# LPDDR3.net
KiCad netlist of a schematic drawn in Altium Designer
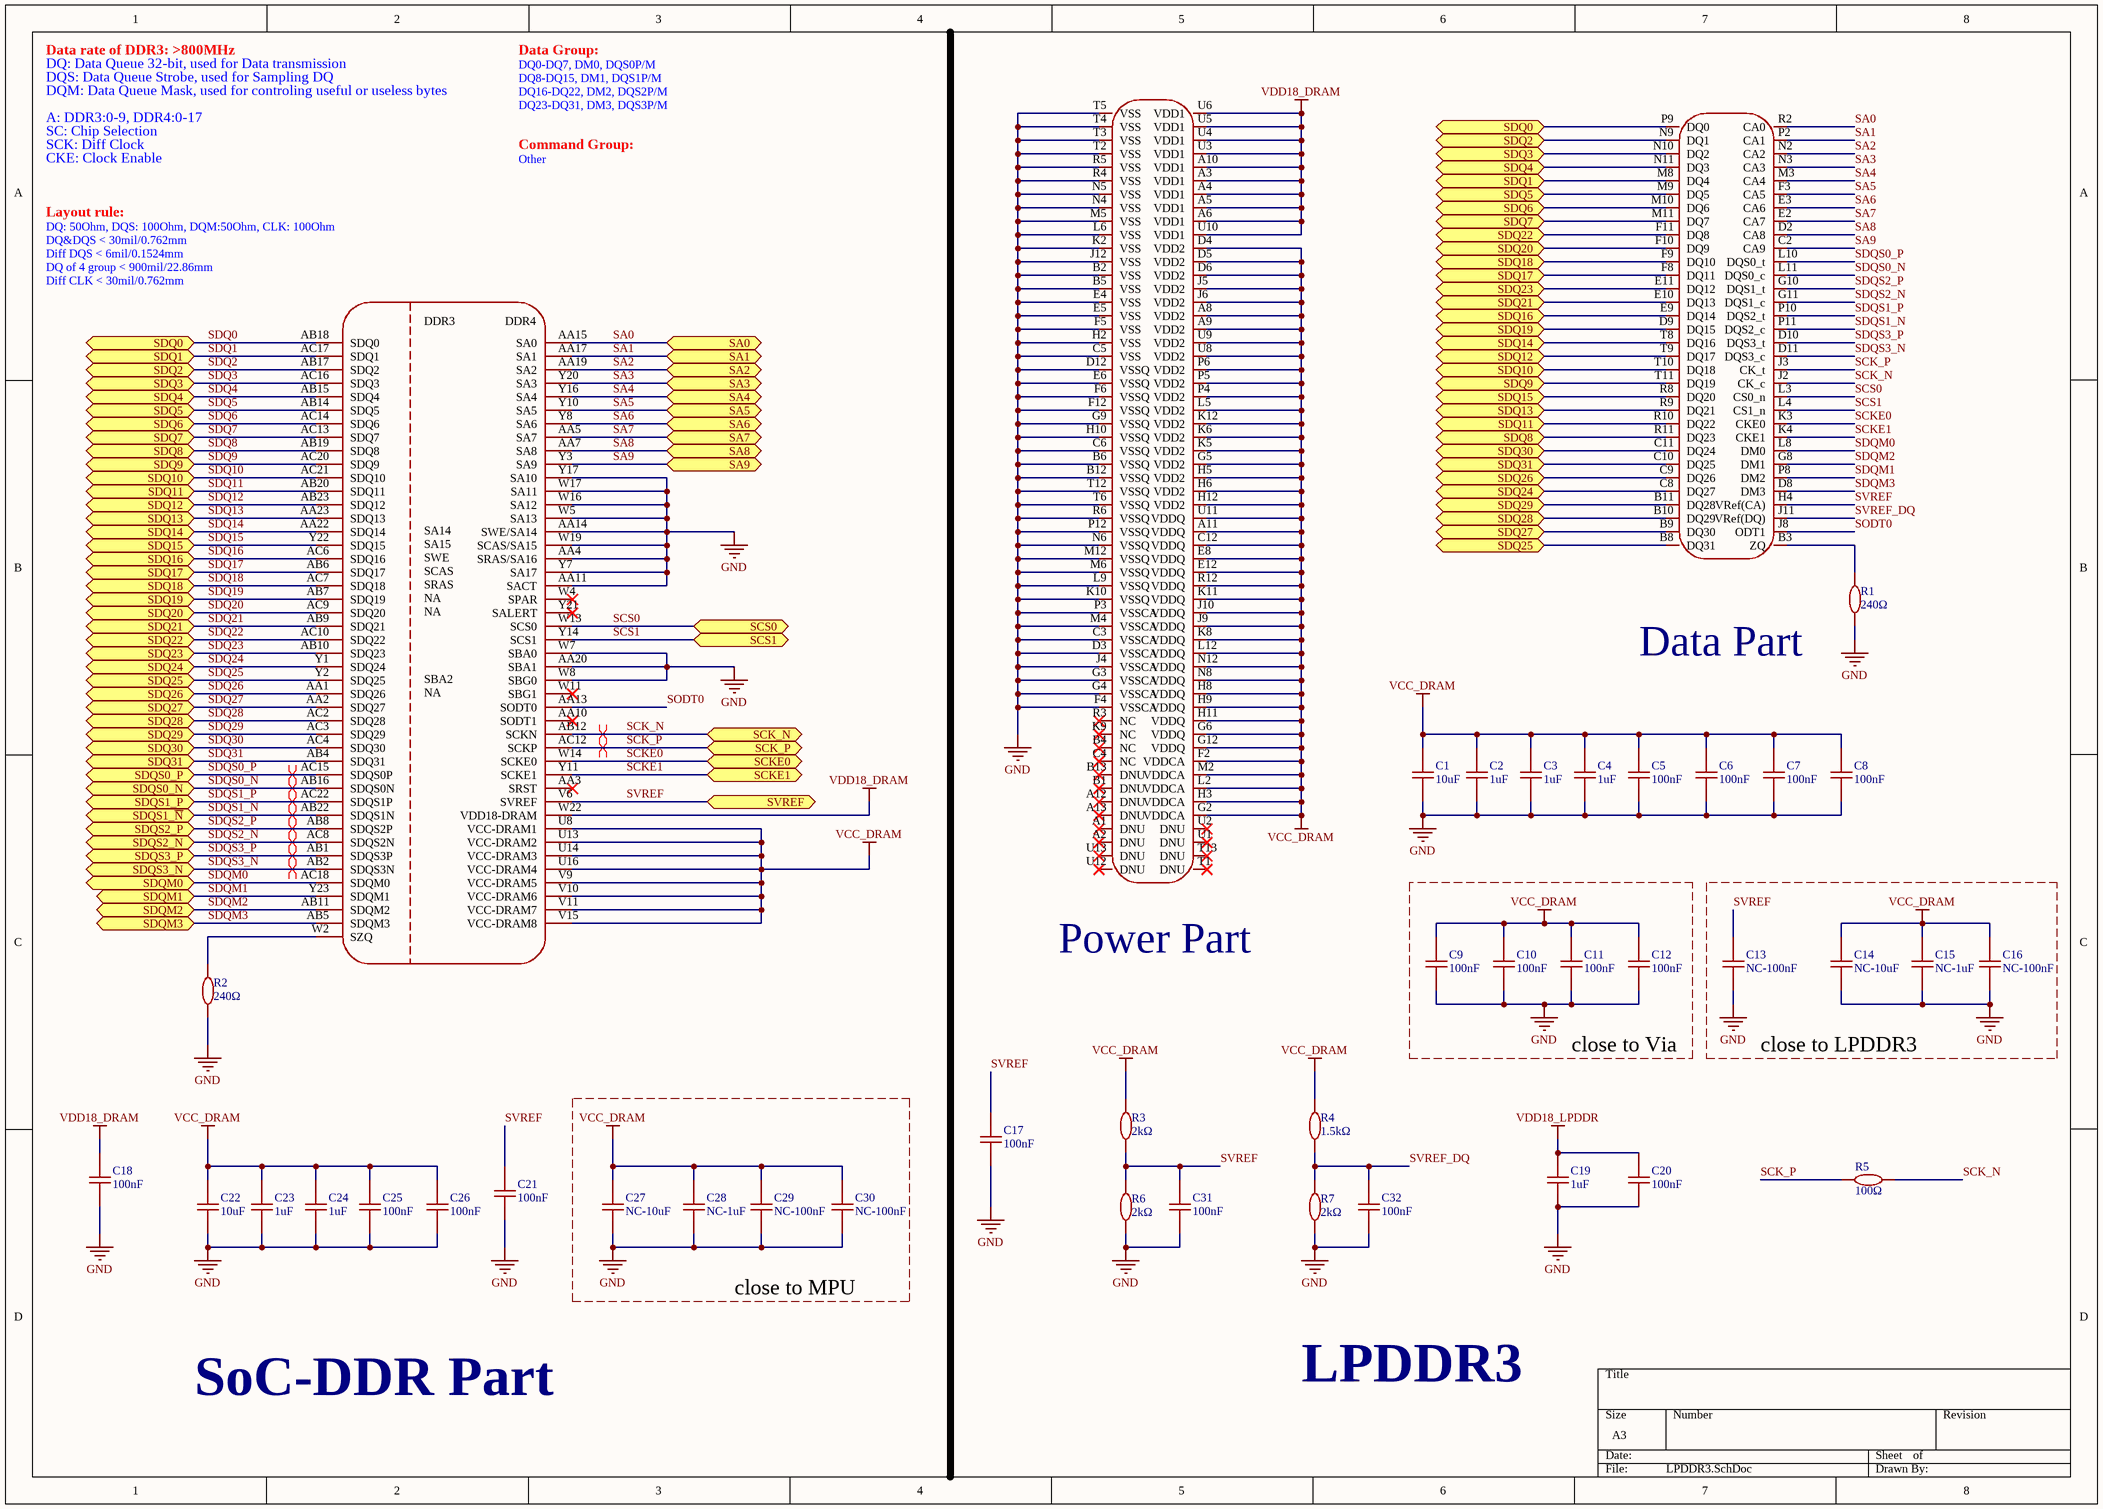
[diagram p0: LPDDR3.SchDoc]

(export (version "E")
  (design (tool "Eeschema 10.0.6"))
  (components
    (comp (ref "C1")
      (value "10uF")
      (footprint "C0603")
      (description "10V 10uF X5R ±10% 0603 Ceramic Capacitors ROHS")
      (libsource (lib "RLC") (part "10uF"))
    )
    (comp (ref "C2")
      (value "1uF")
      (footprint "C0402")
      (description "50V 1uF X5R ±10% 0603 Ceramic Capacitors ROHS")
      (libsource (lib "RLC") (part "1uF"))
    )
    (comp (ref "C3")
      (value "1uF")
      (footprint "C0402")
      (description "50V 1uF X5R ±10% 0603 Ceramic Capacitors ROHS")
      (libsource (lib "RLC") (part "1uF"))
    )
    (comp (ref "C4")
      (value "1uF")
      (footprint "C0402")
      (description "50V 1uF X5R ±10% 0603 Ceramic Capacitors ROHS")
      (libsource (lib "RLC") (part "1uF"))
    )
    (comp (ref "C5")
      (value "100nF")
      (footprint "C0402")
      (description "50V 100nF X7R ±10% 0603 Ceramic Capacitors ROHS")
      (libsource (lib "RLC") (part "100nF"))
    )
    (comp (ref "C6")
      (value "100nF")
      (footprint "C0402")
      (description "50V 100nF X7R ±10% 0603 Ceramic Capacitors ROHS")
      (libsource (lib "RLC") (part "100nF"))
    )
    (comp (ref "C7")
      (value "100nF")
      (footprint "C0402")
      (description "50V 100nF X7R ±10% 0603 Ceramic Capacitors ROHS")
      (libsource (lib "RLC") (part "100nF"))
    )
    (comp (ref "C8")
      (value "100nF")
      (footprint "C0402")
      (description "50V 100nF X7R ±10% 0603 Ceramic Capacitors ROHS")
      (libsource (lib "RLC") (part "100nF"))
    )
    (comp (ref "C9")
      (value "100nF")
      (footprint "C0402")
      (description "50V 100nF X7R ±10% 0603 Ceramic Capacitors ROHS")
      (libsource (lib "RLC") (part "100nF"))
    )
    (comp (ref "C10")
      (value "100nF")
      (footprint "C0402")
      (description "50V 100nF X7R ±10% 0603 Ceramic Capacitors ROHS")
      (libsource (lib "RLC") (part "100nF"))
    )
    (comp (ref "C11")
      (value "100nF")
      (footprint "C0402")
      (description "50V 100nF X7R ±10% 0603 Ceramic Capacitors ROHS")
      (libsource (lib "RLC") (part "100nF"))
    )
    (comp (ref "C12")
      (value "100nF")
      (footprint "C0402")
      (description "50V 100nF X7R ±10% 0603 Ceramic Capacitors ROHS")
      (libsource (lib "RLC") (part "100nF"))
    )
    (comp (ref "C13")
      (value "NC-100nF")
      (footprint "C0402")
      (description "50V 100nF X7R ±10% 0603 Ceramic Capacitors ROHS")
      (libsource (lib "RLC") (part "100nF"))
    )
    (comp (ref "C14")
      (value "NC-10uF")
      (footprint "C0603")
      (description "10V 10uF X5R ±10% 0603 Ceramic Capacitors ROHS")
      (libsource (lib "RLC") (part "10uF"))
    )
    (comp (ref "C15")
      (value "NC-1uF")
      (footprint "C0402")
      (description "50V 1uF X5R ±10% 0603 Ceramic Capacitors ROHS")
      (libsource (lib "RLC") (part "1uF"))
    )
    (comp (ref "C16")
      (value "NC-100nF")
      (footprint "C0402")
      (description "50V 100nF X7R ±10% 0603 Ceramic Capacitors ROHS")
      (libsource (lib "RLC") (part "100nF"))
    )
    (comp (ref "C17")
      (value "100nF")
      (footprint "C0402")
      (description "50V 100nF X7R ±10% 0603 Ceramic Capacitors ROHS")
      (libsource (lib "RLC") (part "100nF"))
    )
    (comp (ref "C18")
      (value "100nF")
      (footprint "C0402")
      (description "50V 100nF X7R ±10% 0603 Ceramic Capacitors ROHS")
      (libsource (lib "RLC") (part "100nF"))
    )
    (comp (ref "C19")
      (value "1uF")
      (footprint "C0402")
      (description "50V 1uF X5R ±10% 0603 Ceramic Capacitors ROHS")
      (libsource (lib "RLC") (part "1uF"))
    )
    (comp (ref "C20")
      (value "100nF")
      (footprint "C0402")
      (description "50V 100nF X7R ±10% 0603 Ceramic Capacitors ROHS")
      (libsource (lib "RLC") (part "100nF"))
    )
    (comp (ref "C21")
      (value "100nF")
      (footprint "C0402")
      (description "50V 100nF X7R ±10% 0603 Ceramic Capacitors ROHS")
      (libsource (lib "RLC") (part "100nF"))
    )
    (comp (ref "C22")
      (value "10uF")
      (footprint "C0603")
      (description "10V 10uF X5R ±10% 0603 Ceramic Capacitors ROHS")
      (libsource (lib "RLC") (part "10uF"))
    )
    (comp (ref "C23")
      (value "1uF")
      (footprint "C0402")
      (description "50V 1uF X5R ±10% 0603 Ceramic Capacitors ROHS")
      (libsource (lib "RLC") (part "1uF"))
    )
    (comp (ref "C24")
      (value "1uF")
      (footprint "C0402")
      (description "50V 1uF X5R ±10% 0603 Ceramic Capacitors ROHS")
      (libsource (lib "RLC") (part "1uF"))
    )
    (comp (ref "C25")
      (value "100nF")
      (footprint "C0402")
      (description "50V 100nF X7R ±10% 0603 Ceramic Capacitors ROHS")
      (libsource (lib "RLC") (part "100nF"))
    )
    (comp (ref "C26")
      (value "100nF")
      (footprint "C0402")
      (description "50V 100nF X7R ±10% 0603 Ceramic Capacitors ROHS")
      (libsource (lib "RLC") (part "100nF"))
    )
    (comp (ref "C27")
      (value "NC-10uF")
      (footprint "C0603")
      (description "10V 10uF X5R ±10% 0603 Ceramic Capacitors ROHS")
      (libsource (lib "RLC") (part "10uF"))
    )
    (comp (ref "C28")
      (value "NC-1uF")
      (footprint "C0402")
      (description "50V 1uF X5R ±10% 0603 Ceramic Capacitors ROHS")
      (libsource (lib "RLC") (part "1uF"))
    )
    (comp (ref "C29")
      (value "NC-100nF")
      (footprint "C0402")
      (description "50V 100nF X7R ±10% 0603 Ceramic Capacitors ROHS")
      (libsource (lib "RLC") (part "100nF"))
    )
    (comp (ref "C30")
      (value "NC-100nF")
      (footprint "C0402")
      (description "50V 100nF X7R ±10% 0603 Ceramic Capacitors ROHS")
      (libsource (lib "RLC") (part "100nF"))
    )
    (comp (ref "C31")
      (value "100nF")
      (footprint "C0402")
      (description "50V 100nF X7R ±10% 0402 Ceramic Capacitors ROHS")
      (libsource (lib "RLC") (part "100nF"))
    )
    (comp (ref "C32")
      (value "100nF")
      (footprint "C0402")
      (description "50V 100nF X7R ±10% 0402 Ceramic Capacitors ROHS")
      (libsource (lib "RLC") (part "100nF"))
    )
    (comp (ref "R1")
      (value "240Ω")
      (footprint "R0402")
      (description "240Ω 62.5mW 50V ±100ppm/℃ Thick Film Resistor ±1% 0402 Chip Resistor - Surface Mount ROHS")
      (libsource (lib "RLC") (part "240Ω"))
    )
    (comp (ref "R2")
      (value "240Ω")
      (footprint "R0402")
      (description "240Ω 62.5mW 50V ±100ppm/℃ Thick Film Resistor ±1% 0402 Chip Resistor - Surface Mount ROHS")
      (libsource (lib "RLC") (part "240Ω"))
    )
    (comp (ref "R3")
      (value "2kΩ")
      (footprint "R0402")
      (description "100mW 2kΩ 75V ±100ppm/℃ Thick Film Resistor ±1% 0402 Chip Resistor - Surface Mount ROHS")
      (libsource (lib "RLC") (part "2kΩ"))
    )
    (comp (ref "R4")
      (value "1.5kΩ")
      (footprint "R0402")
      (description "62.5mW 1.5kΩ 50V ±100ppm/℃ Thick Film Resistor ±1% 0402 Chip Resistor - Surface Mount ROHS")
      (libsource (lib "RLC") (part "1.5kΩ"))
    )
    (comp (ref "R5")
      (value "100Ω")
      (footprint "R0402")
      (description "100Ω 62.5mW 50V ±100ppm/℃ Thick Film Resistor ±1% 0402 Chip Resistor - Surface Mount ROHS")
      (libsource (lib "RLC") (part "100Ω"))
    )
    (comp (ref "R6")
      (value "2kΩ")
      (footprint "R0402")
      (description "100mW 2kΩ 75V ±100ppm/℃ Thick Film Resistor ±1% 0402 Chip Resistor - Surface Mount ROHS")
      (libsource (lib "RLC") (part "2kΩ"))
    )
    (comp (ref "R7")
      (value "2kΩ")
      (footprint "R0402")
      (description "100mW 2kΩ 75V ±100ppm/℃ Thick Film Resistor ±1% 0402 Chip Resistor - Surface Mount ROHS")
      (libsource (lib "RLC") (part "2kΩ"))
    )
    (comp (ref "U1")
      (value "LPDDR3-2G")
      (footprint "FBGA-178_L11.5-W11.0_K4E6E304EC-TL")
      (fields
        (field (name "MANUFACTURER") "SAMSUNG(三星半导体)")
        (field (name "MANUFACTURER PART") "K4E6E304EC-EGCG")
      )
      (libsource (lib "IC") (part "LPDDR3-2G"))
    )
    (comp (ref "U2")
      (value "Allwinner_H6")
      (footprint "BGA451_ALLWINNER_H6")
      (libsource (lib "IC") (part "Allwinner_H6"))
    )
  )
  (nets
    (net (code "1") (name "/SA0") (class "Default")
      (node (ref "U1") (pin "R2") (pinfunction "CA0_R2") (pintype "passive"))
      (node (ref "U2") (pin "AA15") (pinfunction "SA0_AA15") (pintype "passive"))
    )
    (net (code "2") (name "/SA1") (class "Default")
      (node (ref "U1") (pin "P2") (pinfunction "CA1_P2") (pintype "passive"))
      (node (ref "U2") (pin "AA17") (pinfunction "SA1_AA17") (pintype "passive"))
    )
    (net (code "3") (name "/SA2") (class "Default")
      (node (ref "U1") (pin "N2") (pinfunction "CA2_N2") (pintype "passive"))
      (node (ref "U2") (pin "AA19") (pinfunction "SA2_AA19") (pintype "passive"))
    )
    (net (code "4") (name "/SA3") (class "Default")
      (node (ref "U1") (pin "N3") (pinfunction "CA3_N3") (pintype "passive"))
      (node (ref "U2") (pin "Y20") (pinfunction "SA3_Y20") (pintype "passive"))
    )
    (net (code "5") (name "/SA4") (class "Default")
      (node (ref "U1") (pin "M3") (pinfunction "CA4_M3") (pintype "passive"))
      (node (ref "U2") (pin "Y16") (pinfunction "SA4_Y16") (pintype "passive"))
    )
    (net (code "6") (name "/SA5") (class "Default")
      (node (ref "U1") (pin "F3") (pinfunction "CA5_F3") (pintype "passive"))
      (node (ref "U2") (pin "Y10") (pinfunction "SA5_Y10") (pintype "passive"))
    )
    (net (code "7") (name "/SA6") (class "Default")
      (node (ref "U1") (pin "E3") (pinfunction "CA6_E3") (pintype "passive"))
      (node (ref "U2") (pin "Y8") (pinfunction "SA6_Y8") (pintype "passive"))
    )
    (net (code "8") (name "/SA7") (class "Default")
      (node (ref "U1") (pin "E2") (pinfunction "CA7_E2") (pintype "passive"))
      (node (ref "U2") (pin "AA5") (pinfunction "SA7_AA5") (pintype "passive"))
    )
    (net (code "9") (name "/SA8") (class "Default")
      (node (ref "U1") (pin "D2") (pinfunction "CA8_D2") (pintype "passive"))
      (node (ref "U2") (pin "AA7") (pinfunction "SA8_AA7") (pintype "passive"))
    )
    (net (code "10") (name "/SA9") (class "Default")
      (node (ref "U1") (pin "C2") (pinfunction "CA9_C2") (pintype "passive"))
      (node (ref "U2") (pin "Y3") (pinfunction "SA9_Y3") (pintype "passive"))
    )
    (net (code "11") (name "/SCKE0") (class "Default")
      (node (ref "U1") (pin "K3") (pinfunction "CKE0_K3") (pintype "passive"))
      (node (ref "U2") (pin "W14") (pinfunction "SCKE0_W14") (pintype "passive"))
    )
    (net (code "12") (name "/SCKE1") (class "Default")
      (node (ref "U1") (pin "K4") (pinfunction "CKE1_K4") (pintype "passive"))
      (node (ref "U2") (pin "Y11") (pinfunction "SCKE1_Y11") (pintype "passive"))
    )
    (net (code "13") (name "/SCK_N") (class "Default")
      (node (ref "R5") (pin "2") (pinfunction "2_2") (pintype "passive"))
      (node (ref "U1") (pin "J2") (pinfunction "CK_c_J2") (pintype "passive"))
      (node (ref "U2") (pin "AB12") (pinfunction "SCKN_AB12") (pintype "passive"))
    )
    (net (code "14") (name "/SCK_P") (class "Default")
      (node (ref "R5") (pin "1") (pinfunction "1_1") (pintype "passive"))
      (node (ref "U1") (pin "J3") (pinfunction "CK_t_J3") (pintype "passive"))
      (node (ref "U2") (pin "AC12") (pinfunction "SCKP_AC12") (pintype "passive"))
    )
    (net (code "15") (name "/SCS0") (class "Default")
      (node (ref "U1") (pin "L3") (pinfunction "CS0_n_L3") (pintype "passive"))
      (node (ref "U2") (pin "W13") (pinfunction "SCS0_W13") (pintype "passive"))
    )
    (net (code "16") (name "/SCS1") (class "Default")
      (node (ref "U1") (pin "L4") (pinfunction "CS1_n_L4") (pintype "passive"))
      (node (ref "U2") (pin "Y14") (pinfunction "SCS1_Y14") (pintype "passive"))
    )
    (net (code "17") (name "/SDQ0") (class "Default")
      (node (ref "U1") (pin "P9") (pinfunction "DQ0_P9") (pintype "passive"))
      (node (ref "U2") (pin "AB18") (pinfunction "SDQ0_AB18") (pintype "passive"))
    )
    (net (code "18") (name "/SDQ1") (class "Default")
      (node (ref "U1") (pin "M8") (pinfunction "DQ4_M8") (pintype "passive"))
      (node (ref "U2") (pin "AC17") (pinfunction "SDQ1_AC17") (pintype "passive"))
    )
    (net (code "19") (name "/SDQ2") (class "Default")
      (node (ref "U1") (pin "N9") (pinfunction "DQ1_N9") (pintype "passive"))
      (node (ref "U2") (pin "AB17") (pinfunction "SDQ2_AB17") (pintype "passive"))
    )
    (net (code "20") (name "/SDQ3") (class "Default")
      (node (ref "U1") (pin "N10") (pinfunction "DQ2_N10") (pintype "passive"))
      (node (ref "U2") (pin "AC16") (pinfunction "SDQ3_AC16") (pintype "passive"))
    )
    (net (code "21") (name "/SDQ4") (class "Default")
      (node (ref "U1") (pin "N11") (pinfunction "DQ3_N11") (pintype "passive"))
      (node (ref "U2") (pin "AB15") (pinfunction "SDQ4_AB15") (pintype "passive"))
    )
    (net (code "22") (name "/SDQ5") (class "Default")
      (node (ref "U1") (pin "M9") (pinfunction "DQ5_M9") (pintype "passive"))
      (node (ref "U2") (pin "AB14") (pinfunction "SDQ5_AB14") (pintype "passive"))
    )
    (net (code "23") (name "/SDQ6") (class "Default")
      (node (ref "U1") (pin "M10") (pinfunction "DQ6_M10") (pintype "passive"))
      (node (ref "U2") (pin "AC14") (pinfunction "SDQ6_AC14") (pintype "passive"))
    )
    (net (code "24") (name "/SDQ7") (class "Default")
      (node (ref "U1") (pin "M11") (pinfunction "DQ7_M11") (pintype "passive"))
      (node (ref "U2") (pin "AC13") (pinfunction "SDQ7_AC13") (pintype "passive"))
    )
    (net (code "25") (name "/SDQ8") (class "Default")
      (node (ref "U1") (pin "R11") (pinfunction "DQ23_R11") (pintype "passive"))
      (node (ref "U2") (pin "AB19") (pinfunction "SDQ8_AB19") (pintype "passive"))
    )
    (net (code "26") (name "/SDQ9") (class "Default")
      (node (ref "U1") (pin "T11") (pinfunction "DQ19_T11") (pintype "passive"))
      (node (ref "U2") (pin "AC20") (pinfunction "SDQ9_AC20") (pintype "passive"))
    )
    (net (code "27") (name "/SDQ10") (class "Default")
      (node (ref "U1") (pin "T10") (pinfunction "DQ18_T10") (pintype "passive"))
      (node (ref "U2") (pin "AC21") (pinfunction "SDQ10_AC21") (pintype "passive"))
    )
    (net (code "28") (name "/SDQ11") (class "Default")
      (node (ref "U1") (pin "R10") (pinfunction "DQ22_R10") (pintype "passive"))
      (node (ref "U2") (pin "AB20") (pinfunction "SDQ11_AB20") (pintype "passive"))
    )
    (net (code "29") (name "/SDQ12") (class "Default")
      (node (ref "U1") (pin "T9") (pinfunction "DQ17_T9") (pintype "passive"))
      (node (ref "U2") (pin "AB23") (pinfunction "SDQ12_AB23") (pintype "passive"))
    )
    (net (code "30") (name "/SDQ13") (class "Default")
      (node (ref "U1") (pin "R9") (pinfunction "DQ21_R9") (pintype "passive"))
      (node (ref "U2") (pin "AA23") (pinfunction "SDQ13_AA23") (pintype "passive"))
    )
    (net (code "31") (name "/SDQ14") (class "Default")
      (node (ref "U1") (pin "T8") (pinfunction "DQ16_T8") (pintype "passive"))
      (node (ref "U2") (pin "AA22") (pinfunction "SDQ14_AA22") (pintype "passive"))
    )
    (net (code "32") (name "/SDQ15") (class "Default")
      (node (ref "U1") (pin "R8") (pinfunction "DQ20_R8") (pintype "passive"))
      (node (ref "U2") (pin "Y22") (pinfunction "SDQ15_Y22") (pintype "passive"))
    )
    (net (code "33") (name "/SDQ16") (class "Default")
      (node (ref "U1") (pin "E9") (pinfunction "DQ14_E9") (pintype "passive"))
      (node (ref "U2") (pin "AC6") (pinfunction "SDQ16_AC6") (pintype "passive"))
    )
    (net (code "34") (name "/SDQ17") (class "Default")
      (node (ref "U1") (pin "F8") (pinfunction "DQ11_F8") (pintype "passive"))
      (node (ref "U2") (pin "AB6") (pinfunction "SDQ17_AB6") (pintype "passive"))
    )
    (net (code "35") (name "/SDQ18") (class "Default")
      (node (ref "U1") (pin "F9") (pinfunction "DQ10_F9") (pintype "passive"))
      (node (ref "U2") (pin "AC7") (pinfunction "SDQ18_AC7") (pintype "passive"))
    )
    (net (code "36") (name "/SDQ19") (class "Default")
      (node (ref "U1") (pin "D9") (pinfunction "DQ15_D9") (pintype "passive"))
      (node (ref "U2") (pin "AB7") (pinfunction "SDQ19_AB7") (pintype "passive"))
    )
    (net (code "37") (name "/SDQ20") (class "Default")
      (node (ref "U1") (pin "F10") (pinfunction "DQ9_F10") (pintype "passive"))
      (node (ref "U2") (pin "AC9") (pinfunction "SDQ20_AC9") (pintype "passive"))
    )
    (net (code "38") (name "/SDQ21") (class "Default")
      (node (ref "U1") (pin "E10") (pinfunction "DQ13_E10") (pintype "passive"))
      (node (ref "U2") (pin "AB9") (pinfunction "SDQ21_AB9") (pintype "passive"))
    )
    (net (code "39") (name "/SDQ22") (class "Default")
      (node (ref "U1") (pin "F11") (pinfunction "DQ8_F11") (pintype "passive"))
      (node (ref "U2") (pin "AC10") (pinfunction "SDQ22_AC10") (pintype "passive"))
    )
    (net (code "40") (name "/SDQ23") (class "Default")
      (node (ref "U1") (pin "E11") (pinfunction "DQ12_E11") (pintype "passive"))
      (node (ref "U2") (pin "AB10") (pinfunction "SDQ23_AB10") (pintype "passive"))
    )
    (net (code "41") (name "/SDQ24") (class "Default")
      (node (ref "U1") (pin "C8") (pinfunction "DQ27_C8") (pintype "passive"))
      (node (ref "U2") (pin "Y1") (pinfunction "SDQ24_Y1") (pintype "passive"))
    )
    (net (code "42") (name "/SDQ25") (class "Default")
      (node (ref "U1") (pin "B8") (pinfunction "DQ31_B8") (pintype "passive"))
      (node (ref "U2") (pin "Y2") (pinfunction "SDQ25_Y2") (pintype "passive"))
    )
    (net (code "43") (name "/SDQ26") (class "Default")
      (node (ref "U1") (pin "C9") (pinfunction "DQ26_C9") (pintype "passive"))
      (node (ref "U2") (pin "AA1") (pinfunction "SDQ26_AA1") (pintype "passive"))
    )
    (net (code "44") (name "/SDQ27") (class "Default")
      (node (ref "U1") (pin "B9") (pinfunction "DQ30_B9") (pintype "passive"))
      (node (ref "U2") (pin "AA2") (pinfunction "SDQ27_AA2") (pintype "passive"))
    )
    (net (code "45") (name "/SDQ28") (class "Default")
      (node (ref "U1") (pin "B10") (pinfunction "DQ29_B10") (pintype "passive"))
      (node (ref "U2") (pin "AC2") (pinfunction "SDQ28_AC2") (pintype "passive"))
    )
    (net (code "46") (name "/SDQ29") (class "Default")
      (node (ref "U1") (pin "B11") (pinfunction "DQ28_B11") (pintype "passive"))
      (node (ref "U2") (pin "AC3") (pinfunction "SDQ29_AC3") (pintype "passive"))
    )
    (net (code "47") (name "/SDQ30") (class "Default")
      (node (ref "U1") (pin "C11") (pinfunction "DQ24_C11") (pintype "passive"))
      (node (ref "U2") (pin "AC4") (pinfunction "SDQ30_AC4") (pintype "passive"))
    )
    (net (code "48") (name "/SDQ31") (class "Default")
      (node (ref "U1") (pin "C10") (pinfunction "DQ25_C10") (pintype "passive"))
      (node (ref "U2") (pin "AB4") (pinfunction "SDQ31_AB4") (pintype "passive"))
    )
    (net (code "49") (name "/SDQM0") (class "Default")
      (node (ref "U1") (pin "L8") (pinfunction "DM0_L8") (pintype "passive"))
      (node (ref "U2") (pin "AC18") (pinfunction "SDQM0_AC18") (pintype "passive"))
    )
    (net (code "50") (name "/SDQM1") (class "Default")
      (node (ref "U1") (pin "P8") (pinfunction "DM2_P8") (pintype "passive"))
      (node (ref "U2") (pin "Y23") (pinfunction "SDQM1_Y23") (pintype "passive"))
    )
    (net (code "51") (name "/SDQM2") (class "Default")
      (node (ref "U1") (pin "G8") (pinfunction "DM1_G8") (pintype "passive"))
      (node (ref "U2") (pin "AB11") (pinfunction "SDQM2_AB11") (pintype "passive"))
    )
    (net (code "52") (name "/SDQM3") (class "Default")
      (node (ref "U1") (pin "D8") (pinfunction "DM3_D8") (pintype "passive"))
      (node (ref "U2") (pin "AB5") (pinfunction "SDQM3_AB5") (pintype "passive"))
    )
    (net (code "53") (name "/SDQS0_N") (class "Default")
      (node (ref "U1") (pin "L11") (pinfunction "DQS0_c_L11") (pintype "passive"))
      (node (ref "U2") (pin "AB16") (pinfunction "SDQS0N_AB16") (pintype "passive"))
    )
    (net (code "54") (name "/SDQS0_P") (class "Default")
      (node (ref "U1") (pin "L10") (pinfunction "DQS0_t_L10") (pintype "passive"))
      (node (ref "U2") (pin "AC15") (pinfunction "SDQS0P_AC15") (pintype "passive"))
    )
    (net (code "55") (name "/SDQS1_N") (class "Default")
      (node (ref "U1") (pin "P11") (pinfunction "DQS2_c_P11") (pintype "passive"))
      (node (ref "U2") (pin "AB22") (pinfunction "SDQS1N_AB22") (pintype "passive"))
    )
    (net (code "56") (name "/SDQS1_P") (class "Default")
      (node (ref "U1") (pin "P10") (pinfunction "DQS2_t_P10") (pintype "passive"))
      (node (ref "U2") (pin "AC22") (pinfunction "SDQS1P_AC22") (pintype "passive"))
    )
    (net (code "57") (name "/SDQS2_N") (class "Default")
      (node (ref "U1") (pin "G11") (pinfunction "DQS1_c_G11") (pintype "passive"))
      (node (ref "U2") (pin "AC8") (pinfunction "SDQS2N_AC8") (pintype "passive"))
    )
    (net (code "58") (name "/SDQS2_P") (class "Default")
      (node (ref "U1") (pin "G10") (pinfunction "DQS1_t_G10") (pintype "passive"))
      (node (ref "U2") (pin "AB8") (pinfunction "SDQS2P_AB8") (pintype "passive"))
    )
    (net (code "59") (name "/SDQS3_N") (class "Default")
      (node (ref "U1") (pin "D11") (pinfunction "DQS3_c_D11") (pintype "passive"))
      (node (ref "U2") (pin "AB2") (pinfunction "SDQS3N_AB2") (pintype "passive"))
    )
    (net (code "60") (name "/SDQS3_P") (class "Default")
      (node (ref "U1") (pin "D10") (pinfunction "DQS3_t_D10") (pintype "passive"))
      (node (ref "U2") (pin "AB1") (pinfunction "SDQS3P_AB1") (pintype "passive"))
    )
    (net (code "61") (name "/SODT0") (class "Default")
      (node (ref "U1") (pin "J8") (pinfunction "ODT1_J8") (pintype "passive"))
      (node (ref "U2") (pin "AA13") (pinfunction "SODT0_AA13") (pintype "passive"))
    )
    (net (code "62") (name "/SVREF") (class "Default")
      (node (ref "C13") (pin "2") (pinfunction "2_2") (pintype "passive"))
      (node (ref "C17") (pin "2") (pinfunction "2_2") (pintype "passive"))
      (node (ref "C21") (pin "2") (pinfunction "2_2") (pintype "passive"))
      (node (ref "C31") (pin "2") (pinfunction "2_2") (pintype "passive"))
      (node (ref "R3") (pin "1") (pinfunction "1_1") (pintype "passive"))
      (node (ref "R6") (pin "2") (pinfunction "2_2") (pintype "passive"))
      (node (ref "U1") (pin "H4") (pinfunction "VRef(CA)_H4") (pintype "passive"))
      (node (ref "U2") (pin "V6") (pinfunction "SVREF_V6") (pintype "passive"))
    )
    (net (code "63") (name "/SVREF_DQ") (class "Default")
      (node (ref "C32") (pin "2") (pinfunction "2_2") (pintype "passive"))
      (node (ref "R4") (pin "1") (pinfunction "1_1") (pintype "passive"))
      (node (ref "R7") (pin "2") (pinfunction "2_2") (pintype "passive"))
      (node (ref "U1") (pin "J11") (pinfunction "VRef(DQ)_J11") (pintype "passive"))
    )
    (net (code "64") (name "GND") (class "Default")
      (node (ref "C1") (pin "1") (pinfunction "1_1") (pintype "passive"))
      (node (ref "C10") (pin "1") (pinfunction "1_1") (pintype "passive"))
      (node (ref "C11") (pin "1") (pinfunction "1_1") (pintype "passive"))
      (node (ref "C12") (pin "1") (pinfunction "1_1") (pintype "passive"))
      (node (ref "C13") (pin "1") (pinfunction "1_1") (pintype "passive"))
      (node (ref "C14") (pin "1") (pinfunction "1_1") (pintype "passive"))
      (node (ref "C15") (pin "1") (pinfunction "1_1") (pintype "passive"))
      (node (ref "C16") (pin "1") (pinfunction "1_1") (pintype "passive"))
      (node (ref "C17") (pin "1") (pinfunction "1_1") (pintype "passive"))
      (node (ref "C18") (pin "1") (pinfunction "1_1") (pintype "passive"))
      (node (ref "C19") (pin "1") (pinfunction "1_1") (pintype "passive"))
      (node (ref "C2") (pin "1") (pinfunction "1_1") (pintype "passive"))
      (node (ref "C20") (pin "1") (pinfunction "1_1") (pintype "passive"))
      (node (ref "C21") (pin "1") (pinfunction "1_1") (pintype "passive"))
      (node (ref "C22") (pin "1") (pinfunction "1_1") (pintype "passive"))
      (node (ref "C23") (pin "1") (pinfunction "1_1") (pintype "passive"))
      (node (ref "C24") (pin "1") (pinfunction "1_1") (pintype "passive"))
      (node (ref "C25") (pin "1") (pinfunction "1_1") (pintype "passive"))
      (node (ref "C26") (pin "1") (pinfunction "1_1") (pintype "passive"))
      (node (ref "C27") (pin "1") (pinfunction "1_1") (pintype "passive"))
      (node (ref "C28") (pin "1") (pinfunction "1_1") (pintype "passive"))
      (node (ref "C29") (pin "1") (pinfunction "1_1") (pintype "passive"))
      (node (ref "C3") (pin "1") (pinfunction "1_1") (pintype "passive"))
      (node (ref "C30") (pin "1") (pinfunction "1_1") (pintype "passive"))
      (node (ref "C31") (pin "1") (pinfunction "1_1") (pintype "passive"))
      (node (ref "C32") (pin "1") (pinfunction "1_1") (pintype "passive"))
      (node (ref "C4") (pin "1") (pinfunction "1_1") (pintype "passive"))
      (node (ref "C5") (pin "1") (pinfunction "1_1") (pintype "passive"))
      (node (ref "C6") (pin "1") (pinfunction "1_1") (pintype "passive"))
      (node (ref "C7") (pin "1") (pinfunction "1_1") (pintype "passive"))
      (node (ref "C8") (pin "1") (pinfunction "1_1") (pintype "passive"))
      (node (ref "C9") (pin "1") (pinfunction "1_1") (pintype "passive"))
      (node (ref "R1") (pin "1") (pinfunction "1_1") (pintype "passive"))
      (node (ref "R2") (pin "1") (pinfunction "1_1") (pintype "passive"))
      (node (ref "R6") (pin "1") (pinfunction "1_1") (pintype "passive"))
      (node (ref "R7") (pin "1") (pinfunction "1_1") (pintype "passive"))
      (node (ref "U1") (pin "B12") (pinfunction "VSSQ_B12") (pintype "passive"))
      (node (ref "U1") (pin "B2") (pinfunction "VSS_B2") (pintype "passive"))
      (node (ref "U1") (pin "B5") (pinfunction "VSS_B5") (pintype "passive"))
      (node (ref "U1") (pin "B6") (pinfunction "VSSQ_B6") (pintype "passive"))
      (node (ref "U1") (pin "C3") (pinfunction "VSSCA_C3") (pintype "passive"))
      (node (ref "U1") (pin "C5") (pinfunction "VSS_C5") (pintype "passive"))
      (node (ref "U1") (pin "C6") (pinfunction "VSSQ_C6") (pintype "passive"))
      (node (ref "U1") (pin "D12") (pinfunction "VSSQ_D12") (pintype "passive"))
      (node (ref "U1") (pin "D3") (pinfunction "VSSCA_D3") (pintype "passive"))
      (node (ref "U1") (pin "E4") (pinfunction "VSS_E4") (pintype "passive"))
      (node (ref "U1") (pin "E5") (pinfunction "VSS_E5") (pintype "passive"))
      (node (ref "U1") (pin "E6") (pinfunction "VSSQ_E6") (pintype "passive"))
      (node (ref "U1") (pin "F12") (pinfunction "VSSQ_F12") (pintype "passive"))
      (node (ref "U1") (pin "F4") (pinfunction "VSSCA_F4") (pintype "passive"))
      (node (ref "U1") (pin "F5") (pinfunction "VSS_F5") (pintype "passive"))
      (node (ref "U1") (pin "F6") (pinfunction "VSSQ_F6") (pintype "passive"))
      (node (ref "U1") (pin "G3") (pinfunction "VSSCA_G3") (pintype "passive"))
      (node (ref "U1") (pin "G4") (pinfunction "VSSCA_G4") (pintype "passive"))
      (node (ref "U1") (pin "G9") (pinfunction "VSSQ_G9") (pintype "passive"))
      (node (ref "U1") (pin "H10") (pinfunction "VSSQ_H10") (pintype "passive"))
      (node (ref "U1") (pin "H2") (pinfunction "VSS_H2") (pintype "passive"))
      (node (ref "U1") (pin "J12") (pinfunction "VSS_J12") (pintype "passive"))
      (node (ref "U1") (pin "J4") (pinfunction "VSSCA_J4") (pintype "passive"))
      (node (ref "U1") (pin "K10") (pinfunction "VSSQ_K10") (pintype "passive"))
      (node (ref "U1") (pin "K2") (pinfunction "VSS_K2") (pintype "passive"))
      (node (ref "U1") (pin "L6") (pinfunction "VSS_L6") (pintype "passive"))
      (node (ref "U1") (pin "L9") (pinfunction "VSSQ_L9") (pintype "passive"))
      (node (ref "U1") (pin "M12") (pinfunction "VSSQ_M12") (pintype "passive"))
      (node (ref "U1") (pin "M4") (pinfunction "VSSCA_M4") (pintype "passive"))
      (node (ref "U1") (pin "M5") (pinfunction "VSS_M5") (pintype "passive"))
      (node (ref "U1") (pin "M6") (pinfunction "VSSQ_M6") (pintype "passive"))
      (node (ref "U1") (pin "N4") (pinfunction "VSS_N4") (pintype "passive"))
      (node (ref "U1") (pin "N5") (pinfunction "VSS_N5") (pintype "passive"))
      (node (ref "U1") (pin "N6") (pinfunction "VSSQ_N6") (pintype "passive"))
      (node (ref "U1") (pin "P12") (pinfunction "VSSQ_P12") (pintype "passive"))
      (node (ref "U1") (pin "P3") (pinfunction "VSSCA_P3") (pintype "passive"))
      (node (ref "U1") (pin "R4") (pinfunction "VSS_R4") (pintype "passive"))
      (node (ref "U1") (pin "R5") (pinfunction "VSS_R5") (pintype "passive"))
      (node (ref "U1") (pin "R6") (pinfunction "VSSQ_R6") (pintype "passive"))
      (node (ref "U1") (pin "T12") (pinfunction "VSSQ_T12") (pintype "passive"))
      (node (ref "U1") (pin "T2") (pinfunction "VSS_T2") (pintype "passive"))
      (node (ref "U1") (pin "T3") (pinfunction "VSS_T3") (pintype "passive"))
      (node (ref "U1") (pin "T4") (pinfunction "VSS_T4") (pintype "passive"))
      (node (ref "U1") (pin "T5") (pinfunction "VSS_T5") (pintype "passive"))
      (node (ref "U1") (pin "T6") (pinfunction "VSSQ_T6") (pintype "passive"))
      (node (ref "U2") (pin "AA11") (pinfunction "SACT_AA11") (pintype "passive"))
      (node (ref "U2") (pin "AA14") (pinfunction "SWE/SA14_AA14") (pintype "passive"))
      (node (ref "U2") (pin "AA20") (pinfunction "SBA1_AA20") (pintype "passive"))
      (node (ref "U2") (pin "AA4") (pinfunction "SRAS/SA16_AA4") (pintype "passive"))
      (node (ref "U2") (pin "W16") (pinfunction "SA12_W16") (pintype "passive"))
      (node (ref "U2") (pin "W17") (pinfunction "SA11_W17") (pintype "passive"))
      (node (ref "U2") (pin "W19") (pinfunction "SCAS/SA15_W19") (pintype "passive"))
      (node (ref "U2") (pin "W5") (pinfunction "SA13_W5") (pintype "passive"))
      (node (ref "U2") (pin "W7") (pinfunction "SBA0_W7") (pintype "passive"))
      (node (ref "U2") (pin "W8") (pinfunction "SBG0_W8") (pintype "passive"))
      (node (ref "U2") (pin "Y17") (pinfunction "SA10_Y17") (pintype "passive"))
      (node (ref "U2") (pin "Y7") (pinfunction "SA17_Y7") (pintype "passive"))
    )
    (net (code "65") (name "Net-(U1B-ZQ)") (class "Default")
      (node (ref "R1") (pin "2") (pinfunction "2_2") (pintype "passive"))
      (node (ref "U1") (pin "B3") (pinfunction "ZQ_B3") (pintype "passive"))
    )
    (net (code "66") (name "Net-(U2A-SZQ)") (class "Default")
      (node (ref "R2") (pin "2") (pinfunction "2_2") (pintype "passive"))
      (node (ref "U2") (pin "W2") (pinfunction "SZQ_W2") (pintype "passive"))
    )
    (net (code "67") (name "VCC_DRAM") (class "Default")
      (node (ref "C1") (pin "2") (pinfunction "2_2") (pintype "passive"))
      (node (ref "C10") (pin "2") (pinfunction "2_2") (pintype "passive"))
      (node (ref "C11") (pin "2") (pinfunction "2_2") (pintype "passive"))
      (node (ref "C12") (pin "2") (pinfunction "2_2") (pintype "passive"))
      (node (ref "C14") (pin "2") (pinfunction "2_2") (pintype "passive"))
      (node (ref "C15") (pin "2") (pinfunction "2_2") (pintype "passive"))
      (node (ref "C16") (pin "2") (pinfunction "2_2") (pintype "passive"))
      (node (ref "C2") (pin "2") (pinfunction "2_2") (pintype "passive"))
      (node (ref "C22") (pin "2") (pinfunction "2_2") (pintype "passive"))
      (node (ref "C23") (pin "2") (pinfunction "2_2") (pintype "passive"))
      (node (ref "C24") (pin "2") (pinfunction "2_2") (pintype "passive"))
      (node (ref "C25") (pin "2") (pinfunction "2_2") (pintype "passive"))
      (node (ref "C26") (pin "2") (pinfunction "2_2") (pintype "passive"))
      (node (ref "C27") (pin "2") (pinfunction "2_2") (pintype "passive"))
      (node (ref "C28") (pin "2") (pinfunction "2_2") (pintype "passive"))
      (node (ref "C29") (pin "2") (pinfunction "2_2") (pintype "passive"))
      (node (ref "C3") (pin "2") (pinfunction "2_2") (pintype "passive"))
      (node (ref "C30") (pin "2") (pinfunction "2_2") (pintype "passive"))
      (node (ref "C4") (pin "2") (pinfunction "2_2") (pintype "passive"))
      (node (ref "C5") (pin "2") (pinfunction "2_2") (pintype "passive"))
      (node (ref "C6") (pin "2") (pinfunction "2_2") (pintype "passive"))
      (node (ref "C7") (pin "2") (pinfunction "2_2") (pintype "passive"))
      (node (ref "C8") (pin "2") (pinfunction "2_2") (pintype "passive"))
      (node (ref "C9") (pin "2") (pinfunction "2_2") (pintype "passive"))
      (node (ref "R3") (pin "2") (pinfunction "2_2") (pintype "passive"))
      (node (ref "R4") (pin "2") (pinfunction "2_2") (pintype "passive"))
      (node (ref "U1") (pin "A11") (pinfunction "VDDQ_A11") (pintype "passive"))
      (node (ref "U1") (pin "A8") (pinfunction "VDD2_A8") (pintype "passive"))
      (node (ref "U1") (pin "A9") (pinfunction "VDD2_A9") (pintype "passive"))
      (node (ref "U1") (pin "C12") (pinfunction "VDDQ_C12") (pintype "passive"))
      (node (ref "U1") (pin "D4") (pinfunction "VDD2_D4") (pintype "passive"))
      (node (ref "U1") (pin "D5") (pinfunction "VDD2_D5") (pintype "passive"))
      (node (ref "U1") (pin "D6") (pinfunction "VDD2_D6") (pintype "passive"))
      (node (ref "U1") (pin "E12") (pinfunction "VDDQ_E12") (pintype "passive"))
      (node (ref "U1") (pin "E8") (pinfunction "VDDQ_E8") (pintype "passive"))
      (node (ref "U1") (pin "F2") (pinfunction "VDDCA_F2") (pintype "passive"))
      (node (ref "U1") (pin "G12") (pinfunction "VDDQ_G12") (pintype "passive"))
      (node (ref "U1") (pin "G2") (pinfunction "VDDCA_G2") (pintype "passive"))
      (node (ref "U1") (pin "G5") (pinfunction "VDD2_G5") (pintype "passive"))
      (node (ref "U1") (pin "G6") (pinfunction "VDDQ_G6") (pintype "passive"))
      (node (ref "U1") (pin "H11") (pinfunction "VDDQ_H11") (pintype "passive"))
      (node (ref "U1") (pin "H12") (pinfunction "VDD2_H12") (pintype "passive"))
      (node (ref "U1") (pin "H3") (pinfunction "VDDCA_H3") (pintype "passive"))
      (node (ref "U1") (pin "H5") (pinfunction "VDD2_H5") (pintype "passive"))
      (node (ref "U1") (pin "H6") (pinfunction "VDD2_H6") (pintype "passive"))
      (node (ref "U1") (pin "H8") (pinfunction "VDDQ_H8") (pintype "passive"))
      (node (ref "U1") (pin "H9") (pinfunction "VDDQ_H9") (pintype "passive"))
      (node (ref "U1") (pin "J10") (pinfunction "VDDQ_J10") (pintype "passive"))
      (node (ref "U1") (pin "J5") (pinfunction "VDD2_J5") (pintype "passive"))
      (node (ref "U1") (pin "J6") (pinfunction "VDD2_J6") (pintype "passive"))
      (node (ref "U1") (pin "J9") (pinfunction "VDDQ_J9") (pintype "passive"))
      (node (ref "U1") (pin "K11") (pinfunction "VDDQ_K11") (pintype "passive"))
      (node (ref "U1") (pin "K12") (pinfunction "VDD2_K12") (pintype "passive"))
      (node (ref "U1") (pin "K5") (pinfunction "VDD2_K5") (pintype "passive"))
      (node (ref "U1") (pin "K6") (pinfunction "VDD2_K6") (pintype "passive"))
      (node (ref "U1") (pin "K8") (pinfunction "VDDQ_K8") (pintype "passive"))
      (node (ref "U1") (pin "L12") (pinfunction "VDDQ_L12") (pintype "passive"))
      (node (ref "U1") (pin "L2") (pinfunction "VDDCA_L2") (pintype "passive"))
      (node (ref "U1") (pin "L5") (pinfunction "VDD2_L5") (pintype "passive"))
      (node (ref "U1") (pin "M2") (pinfunction "VDDCA_M2") (pintype "passive"))
      (node (ref "U1") (pin "N12") (pinfunction "VDDQ_N12") (pintype "passive"))
      (node (ref "U1") (pin "N8") (pinfunction "VDDQ_N8") (pintype "passive"))
      (node (ref "U1") (pin "P4") (pinfunction "VDD2_P4") (pintype "passive"))
      (node (ref "U1") (pin "P5") (pinfunction "VDD2_P5") (pintype "passive"))
      (node (ref "U1") (pin "P6") (pinfunction "VDD2_P6") (pintype "passive"))
      (node (ref "U1") (pin "R12") (pinfunction "VDDQ_R12") (pintype "passive"))
      (node (ref "U1") (pin "U11") (pinfunction "VDDQ_U11") (pintype "passive"))
      (node (ref "U1") (pin "U8") (pinfunction "VDD2_U8") (pintype "passive"))
      (node (ref "U1") (pin "U9") (pinfunction "VDD2_U9") (pintype "passive"))
      (node (ref "U2") (pin "U13") (pinfunction "VCC-DRAM2_U13") (pintype "passive"))
      (node (ref "U2") (pin "U14") (pinfunction "VCC-DRAM3_U14") (pintype "passive"))
      (node (ref "U2") (pin "U16") (pinfunction "VCC-DRAM4_U16") (pintype "passive"))
      (node (ref "U2") (pin "U8") (pinfunction "VCC-DRAM1_U8") (pintype "passive"))
      (node (ref "U2") (pin "V10") (pinfunction "VCC-DRAM6_V10") (pintype "passive"))
      (node (ref "U2") (pin "V11") (pinfunction "VCC-DRAM7_V11") (pintype "passive"))
      (node (ref "U2") (pin "V15") (pinfunction "VCC-DRAM8_V15") (pintype "passive"))
      (node (ref "U2") (pin "V9") (pinfunction "VCC-DRAM5_V9") (pintype "passive"))
    )
    (net (code "68") (name "VDD18_DRAM") (class "Default")
      (node (ref "C18") (pin "2") (pinfunction "2_2") (pintype "passive"))
      (node (ref "U1") (pin "A10") (pinfunction "VDD1_A10") (pintype "passive"))
      (node (ref "U1") (pin "A3") (pinfunction "VDD1_A3") (pintype "passive"))
      (node (ref "U1") (pin "A4") (pinfunction "VDD1_A4") (pintype "passive"))
      (node (ref "U1") (pin "A5") (pinfunction "VDD1_A5") (pintype "passive"))
      (node (ref "U1") (pin "A6") (pinfunction "VDD1_A6") (pintype "passive"))
      (node (ref "U1") (pin "U10") (pinfunction "VDD1_U10") (pintype "passive"))
      (node (ref "U1") (pin "U3") (pinfunction "VDD1_U3") (pintype "passive"))
      (node (ref "U1") (pin "U4") (pinfunction "VDD1_U4") (pintype "passive"))
      (node (ref "U1") (pin "U5") (pinfunction "VDD1_U5") (pintype "passive"))
      (node (ref "U1") (pin "U6") (pinfunction "VDD1_U6") (pintype "passive"))
      (node (ref "U2") (pin "W22") (pinfunction "VDD18-DRAM_W22") (pintype "passive"))
    )
    (net (code "69") (name "VDD18_LPDDR") (class "Default")
      (node (ref "C19") (pin "2") (pinfunction "2_2") (pintype "passive"))
      (node (ref "C20") (pin "2") (pinfunction "2_2") (pintype "passive"))
    )
    (net (code "70") (name "unconnected-(U1A-DNU-PadA1)") (class "Default")
      (node (ref "U1") (pin "A1") (pinfunction "DNU_A1") (pintype "passive+no_connect"))
    )
    (net (code "71") (name "unconnected-(U1A-DNU-PadA2)") (class "Default")
      (node (ref "U1") (pin "A2") (pinfunction "DNU_A2") (pintype "passive+no_connect"))
    )
    (net (code "72") (name "unconnected-(U1A-DNU-PadA12)") (class "Default")
      (node (ref "U1") (pin "A12") (pinfunction "DNU_A12") (pintype "passive+no_connect"))
    )
    (net (code "73") (name "unconnected-(U1A-DNU-PadA13)") (class "Default")
      (node (ref "U1") (pin "A13") (pinfunction "DNU_A13") (pintype "passive+no_connect"))
    )
    (net (code "74") (name "unconnected-(U1A-DNU-PadB1)") (class "Default")
      (node (ref "U1") (pin "B1") (pinfunction "DNU_B1") (pintype "passive+no_connect"))
    )
    (net (code "75") (name "unconnected-(U1A-DNU-PadB13)") (class "Default")
      (node (ref "U1") (pin "B13") (pinfunction "DNU_B13") (pintype "passive+no_connect"))
    )
    (net (code "76") (name "unconnected-(U1A-DNU-PadT1)") (class "Default")
      (node (ref "U1") (pin "T1") (pinfunction "DNU_T1") (pintype "passive+no_connect"))
    )
    (net (code "77") (name "unconnected-(U1A-DNU-PadT13)") (class "Default")
      (node (ref "U1") (pin "T13") (pinfunction "DNU_T13") (pintype "passive+no_connect"))
    )
    (net (code "78") (name "unconnected-(U1A-DNU-PadU1)") (class "Default")
      (node (ref "U1") (pin "U1") (pinfunction "DNU_U1") (pintype "passive+no_connect"))
    )
    (net (code "79") (name "unconnected-(U1A-DNU-PadU2)") (class "Default")
      (node (ref "U1") (pin "U2") (pinfunction "DNU_U2") (pintype "passive+no_connect"))
    )
    (net (code "80") (name "unconnected-(U1A-DNU-PadU12)") (class "Default")
      (node (ref "U1") (pin "U12") (pinfunction "DNU_U12") (pintype "passive+no_connect"))
    )
    (net (code "81") (name "unconnected-(U1A-DNU-PadU13)") (class "Default")
      (node (ref "U1") (pin "U13") (pinfunction "DNU_U13") (pintype "passive+no_connect"))
    )
    (net (code "82") (name "unconnected-(U1A-NC-PadB4)") (class "Default")
      (node (ref "U1") (pin "B4") (pinfunction "NC_B4") (pintype "passive+no_connect"))
    )
    (net (code "83") (name "unconnected-(U1A-NC-PadC4)") (class "Default")
      (node (ref "U1") (pin "C4") (pinfunction "NC_C4") (pintype "passive+no_connect"))
    )
    (net (code "84") (name "unconnected-(U1A-NC-PadK9)") (class "Default")
      (node (ref "U1") (pin "K9") (pinfunction "NC_K9") (pintype "passive+no_connect"))
    )
    (net (code "85") (name "unconnected-(U1A-NC-PadR3)") (class "Default")
      (node (ref "U1") (pin "R3") (pinfunction "NC_R3") (pintype "passive+no_connect"))
    )
    (net (code "86") (name "unconnected-(U2A-SALERT-PadY21)") (class "Default")
      (node (ref "U2") (pin "Y21") (pinfunction "SALERT_Y21") (pintype "passive+no_connect"))
    )
    (net (code "87") (name "unconnected-(U2A-SBG1-PadW11)") (class "Default")
      (node (ref "U2") (pin "W11") (pinfunction "SBG1_W11") (pintype "passive+no_connect"))
    )
    (net (code "88") (name "unconnected-(U2A-SODT1-PadAA10)") (class "Default")
      (node (ref "U2") (pin "AA10") (pinfunction "SODT1_AA10") (pintype "passive+no_connect"))
    )
    (net (code "89") (name "unconnected-(U2A-SPAR-PadW4)") (class "Default")
      (node (ref "U2") (pin "W4") (pinfunction "SPAR_W4") (pintype "passive+no_connect"))
    )
    (net (code "90") (name "unconnected-(U2A-SRST-PadAA3)") (class "Default")
      (node (ref "U2") (pin "AA3") (pinfunction "SRST_AA3") (pintype "passive+no_connect"))
    )
  )
)
